# RL78G10_FOOT_A2.net
KiCad netlist of a schematic drawn in EAGLE
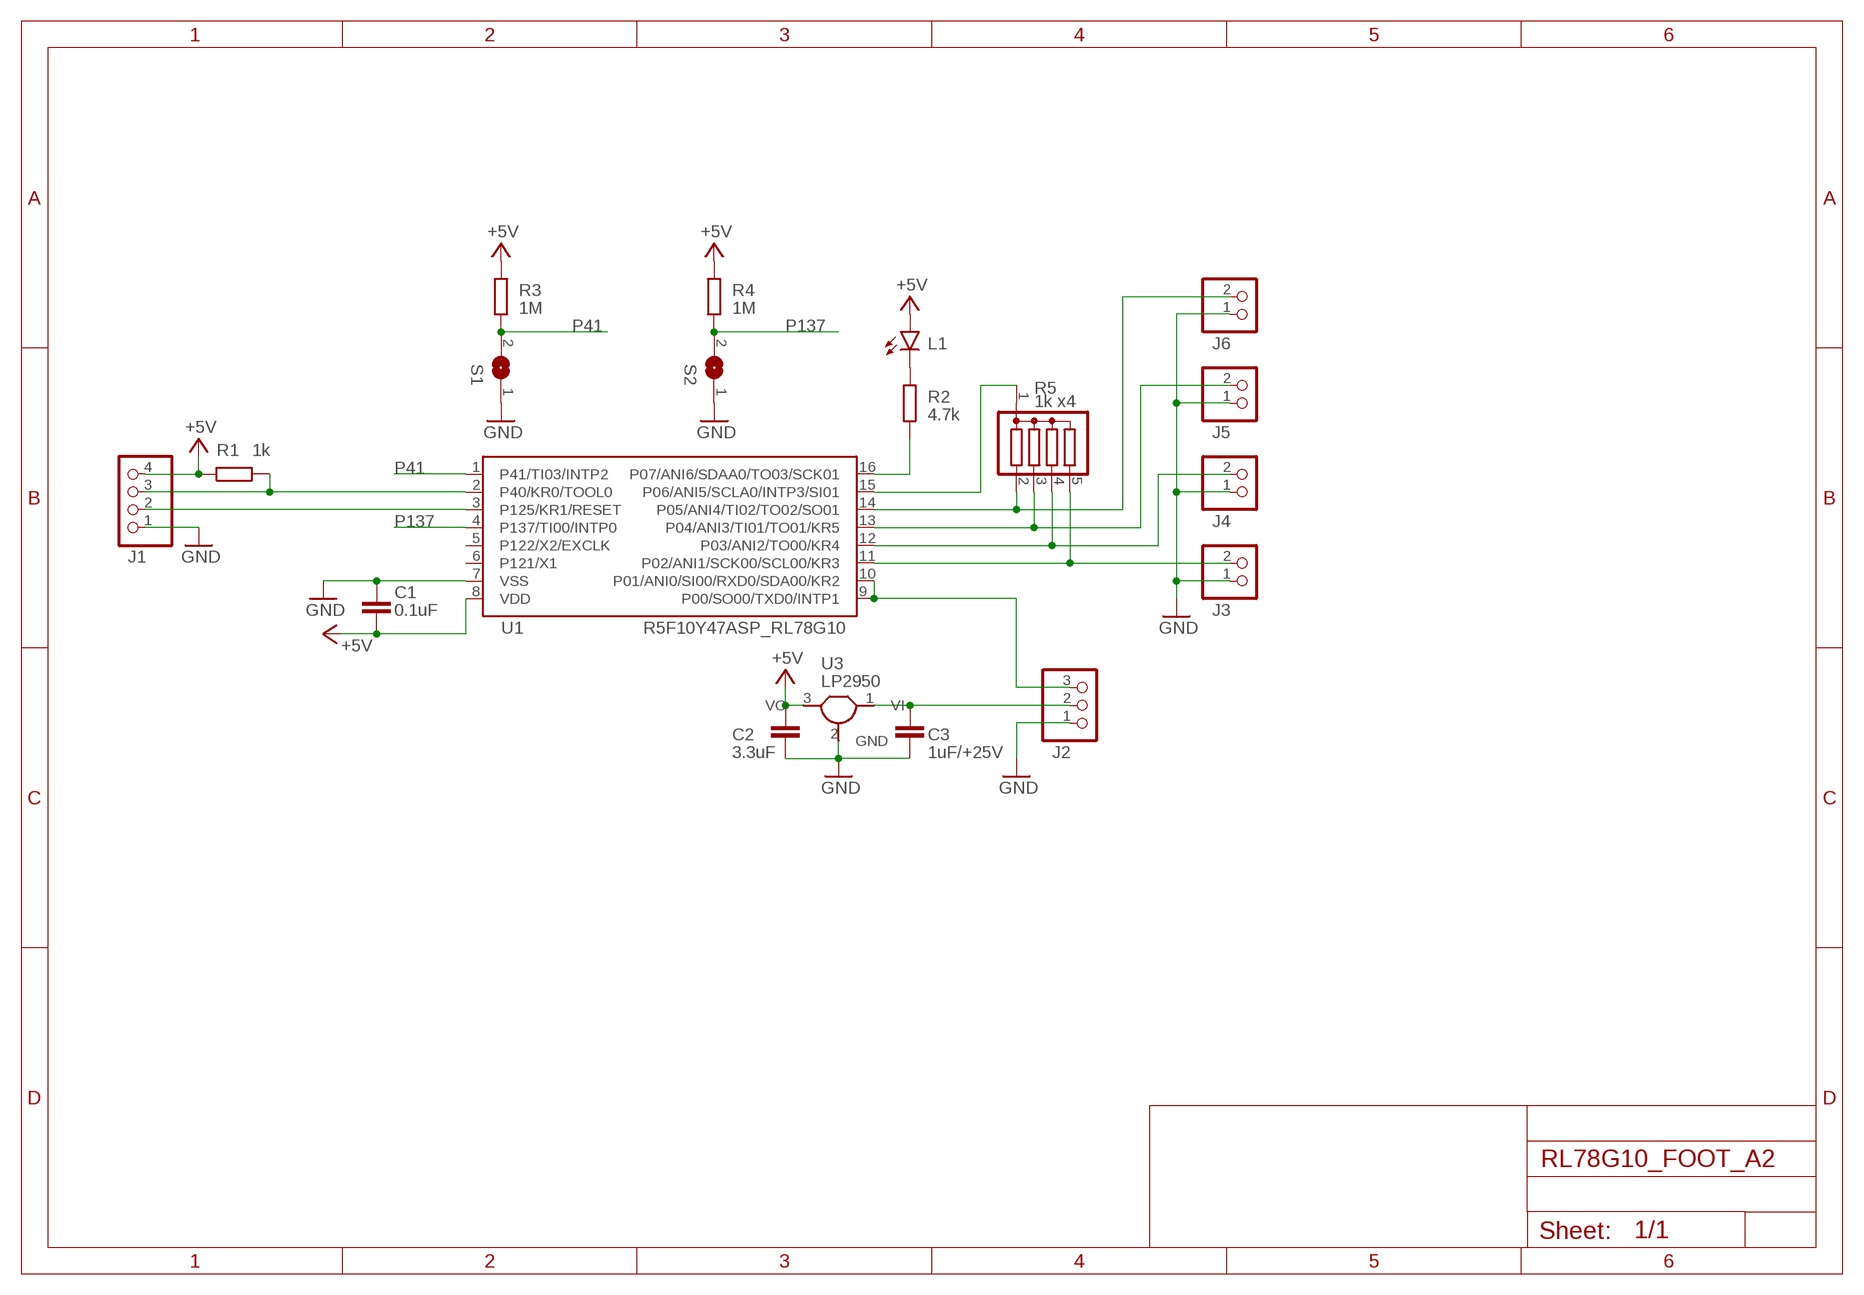
[diagram p0: schematic, sheet 1]

(export (version "E")
  (design (tool "Eeschema 10.0.6"))
  (components
    (comp (ref "C1")
      (value "0.1uF")
      (footprint "eagle-import:C0603")
      (libsource (lib "eagle-import") (part "C-EUC0603"))
    )
    (comp (ref "C2")
      (value "3.3uF")
      (footprint "eagle-import:C0805")
      (libsource (lib "eagle-import") (part "C-EUC0805"))
    )
    (comp (ref "C3")
      (value "1uF/+25V")
      (footprint "eagle-import:C0805")
      (libsource (lib "eagle-import") (part "C-EUC0805"))
    )
    (comp (ref "J1")
      (value "PINHD_1X4")
      (footprint "eagle-import:PINHD_1X04")
      (libsource (lib "eagle-import") (part "PINHD_1X4"))
    )
    (comp (ref "J2")
      (value "PINHD_1X3")
      (footprint "eagle-import:PINHD_1X03")
      (libsource (lib "eagle-import") (part "PINHD_1X3"))
    )
    (comp (ref "J3")
      (value "PINHD_1X2")
      (footprint "eagle-import:PINHD_1X02")
      (libsource (lib "eagle-import") (part "PINHD_1X2"))
    )
    (comp (ref "J4")
      (value "PINHD_1X2")
      (footprint "eagle-import:PINHD_1X02")
      (libsource (lib "eagle-import") (part "PINHD_1X2"))
    )
    (comp (ref "J5")
      (value "PINHD_1X2")
      (footprint "eagle-import:PINHD_1X02")
      (libsource (lib "eagle-import") (part "PINHD_1X2"))
    )
    (comp (ref "J6")
      (value "PINHD_1X2")
      (footprint "eagle-import:PINHD_1X02")
      (libsource (lib "eagle-import") (part "PINHD_1X2"))
    )
    (comp (ref "L1")
      (value "LEDSML0603")
      (footprint "eagle-import:SML0603")
      (libsource (lib "eagle-import") (part "LEDSML0603"))
    )
    (comp (ref "R1")
      (value "1k")
      (footprint "eagle-import:R0603")
      (libsource (lib "eagle-import") (part "R-EU_R0603"))
    )
    (comp (ref "R2")
      (value "4.7k")
      (footprint "eagle-import:R0603")
      (libsource (lib "eagle-import") (part "R-EU_R0603"))
    )
    (comp (ref "R3")
      (value "1M")
      (footprint "eagle-import:R0603")
      (libsource (lib "eagle-import") (part "R-EU_R0603"))
    )
    (comp (ref "R4")
      (value "1M")
      (footprint "eagle-import:R0603")
      (libsource (lib "eagle-import") (part "R-EU_R0603"))
    )
    (comp (ref "R5")
      (value "1k x4")
      (footprint "eagle-import:SIL5")
      (libsource (lib "eagle-import") (part "G04R"))
    )
    (comp (ref "S1")
      (value "SJ-OMINI")
      (footprint "eagle-import:SJ-O")
      (libsource (lib "eagle-import") (part "SJ-OMINI"))
    )
    (comp (ref "S2")
      (value "SJ-OMINI")
      (footprint "eagle-import:SJ-O")
      (libsource (lib "eagle-import") (part "SJ-OMINI"))
    )
    (comp (ref "U1")
      (value "R5F10Y47ASP_RL78G10")
      (footprint "eagle-import:SSOP16")
      (libsource (lib "eagle-import") (part "RL78/G10_16"))
    )
    (comp (ref "U3")
      (value "LP2950")
      (footprint "eagle-import:TO92-")
      (libsource (lib "eagle-import") (part "LP2950"))
    )
  )
  (nets
    (net (code "1") (name "+5V") (class "Default")
      (node (ref "C1") (pin "2") (pinfunction "2_2") (pintype "passive"))
      (node (ref "C2") (pin "1") (pinfunction "1_1") (pintype "passive"))
      (node (ref "J1") (pin "4") (pinfunction "4_4") (pintype "passive"))
      (node (ref "L1") (pin "A") (pinfunction "A_A") (pintype "passive"))
      (node (ref "R1") (pin "1") (pinfunction "1_1") (pintype "passive"))
      (node (ref "R3") (pin "1") (pinfunction "1_1") (pintype "passive"))
      (node (ref "R4") (pin "1") (pinfunction "1_1") (pintype "passive"))
      (node (ref "U1") (pin "8") (pinfunction "VDD_8") (pintype "bidirectional"))
      (node (ref "U3") (pin "3") (pinfunction "VO_3") (pintype "output"))
    )
    (net (code "2") (name "/P41") (class "Default")
      (node (ref "R3") (pin "2") (pinfunction "2_2") (pintype "passive"))
      (node (ref "S1") (pin "2") (pinfunction "2_2") (pintype "passive"))
      (node (ref "U1") (pin "1") (pinfunction "P41/TI03/INTP2_1") (pintype "bidirectional"))
    )
    (net (code "3") (name "/P137") (class "Default")
      (node (ref "R4") (pin "2") (pinfunction "2_2") (pintype "passive"))
      (node (ref "S2") (pin "2") (pinfunction "2_2") (pintype "passive"))
      (node (ref "U1") (pin "4") (pinfunction "P137/TI00/INTP0_4") (pintype "bidirectional"))
    )
    (net (code "4") (name "GND") (class "Default")
      (node (ref "C1") (pin "1") (pinfunction "1_1") (pintype "passive"))
      (node (ref "C2") (pin "2") (pinfunction "2_2") (pintype "passive"))
      (node (ref "C3") (pin "2") (pinfunction "2_2") (pintype "passive"))
      (node (ref "J1") (pin "1") (pinfunction "1_1") (pintype "passive"))
      (node (ref "J2") (pin "1") (pinfunction "1_1") (pintype "passive"))
      (node (ref "J3") (pin "1") (pinfunction "1_1") (pintype "passive"))
      (node (ref "J4") (pin "1") (pinfunction "1_1") (pintype "passive"))
      (node (ref "J5") (pin "1") (pinfunction "1_1") (pintype "passive"))
      (node (ref "J6") (pin "1") (pinfunction "1_1") (pintype "passive"))
      (node (ref "S1") (pin "1") (pinfunction "1_1") (pintype "passive"))
      (node (ref "S2") (pin "1") (pinfunction "1_1") (pintype "passive"))
      (node (ref "U1") (pin "7") (pinfunction "VSS_7") (pintype "bidirectional"))
      (node (ref "U3") (pin "2") (pinfunction "GND_2") (pintype "bidirectional"))
    )
    (net (code "5") (name "Net-(L1-PadC)") (class "Default")
      (node (ref "L1") (pin "C") (pinfunction "C_C") (pintype "passive"))
      (node (ref "R2") (pin "1") (pinfunction "1_1") (pintype "passive"))
    )
    (net (code "6") (name "Net-(U1-P00{slash}SO00{slash}TXD0{slash}INTP1)") (class "Default")
      (node (ref "J2") (pin "3") (pinfunction "3_3") (pintype "passive"))
      (node (ref "U1") (pin "10") (pinfunction "P01/ANI0/SI00/RXD0/SDA00/KR2_10") (pintype "bidirectional"))
      (node (ref "U1") (pin "9") (pinfunction "P00/SO00/TXD0/INTP1_9") (pintype "bidirectional"))
    )
    (net (code "7") (name "Net-(U1-P02{slash}ANI1{slash}SCK00{slash}SCL00{slash}KR3)") (class "Default")
      (node (ref "J3") (pin "2") (pinfunction "2_2") (pintype "passive"))
      (node (ref "R5") (pin "5") (pinfunction "5_5") (pintype "passive"))
      (node (ref "U1") (pin "11") (pinfunction "P02/ANI1/SCK00/SCL00/KR3_11") (pintype "bidirectional"))
    )
    (net (code "8") (name "Net-(U1-P03{slash}ANI2{slash}TO00{slash}KR4)") (class "Default")
      (node (ref "J4") (pin "2") (pinfunction "2_2") (pintype "passive"))
      (node (ref "R5") (pin "4") (pinfunction "4_4") (pintype "passive"))
      (node (ref "U1") (pin "12") (pinfunction "P03/ANI2/TO00/KR4_12") (pintype "bidirectional"))
    )
    (net (code "9") (name "Net-(U1-P04{slash}ANI3{slash}TI01{slash}TO01{slash}KR5)") (class "Default")
      (node (ref "J5") (pin "2") (pinfunction "2_2") (pintype "passive"))
      (node (ref "R5") (pin "3") (pinfunction "3_3") (pintype "passive"))
      (node (ref "U1") (pin "13") (pinfunction "P04/ANI3/TI01/TO01/KR5_13") (pintype "bidirectional"))
    )
    (net (code "10") (name "Net-(U1-P05{slash}ANI4{slash}TI02{slash}TO02{slash}SO01)") (class "Default")
      (node (ref "J6") (pin "2") (pinfunction "2_2") (pintype "passive"))
      (node (ref "R5") (pin "2") (pinfunction "2_2") (pintype "passive"))
      (node (ref "U1") (pin "14") (pinfunction "P05/ANI4/TI02/TO02/SO01_14") (pintype "bidirectional"))
    )
    (net (code "11") (name "Net-(U1-P06{slash}ANI5{slash}SCLA0{slash}INTP3{slash}SI01)") (class "Default")
      (node (ref "R5") (pin "1") (pinfunction "1_1") (pintype "passive"))
      (node (ref "U1") (pin "15") (pinfunction "P06/ANI5/SCLA0/INTP3/SI01_15") (pintype "bidirectional"))
    )
    (net (code "12") (name "Net-(U1-P07{slash}ANI6{slash}SDAA0{slash}TO03{slash}SCK01)") (class "Default")
      (node (ref "R2") (pin "2") (pinfunction "2_2") (pintype "passive"))
      (node (ref "U1") (pin "16") (pinfunction "P07/ANI6/SDAA0/TO03/SCK01_16") (pintype "bidirectional"))
    )
    (net (code "13") (name "Net-(U1-P40{slash}KR0{slash}TOOL0)") (class "Default")
      (node (ref "J1") (pin "3") (pinfunction "3_3") (pintype "passive"))
      (node (ref "R1") (pin "2") (pinfunction "2_2") (pintype "passive"))
      (node (ref "U1") (pin "2") (pinfunction "P40/KR0/TOOL0_2") (pintype "bidirectional"))
    )
    (net (code "14") (name "Net-(U1-P125{slash}KR1{slash}RESET)") (class "Default")
      (node (ref "J1") (pin "2") (pinfunction "2_2") (pintype "passive"))
      (node (ref "U1") (pin "3") (pinfunction "P125/KR1/RESET_3") (pintype "bidirectional"))
    )
    (net (code "15") (name "Net-(U3-VI)") (class "Default")
      (node (ref "C3") (pin "1") (pinfunction "1_1") (pintype "passive"))
      (node (ref "J2") (pin "2") (pinfunction "2_2") (pintype "passive"))
      (node (ref "U3") (pin "1") (pinfunction "VI_1") (pintype "input"))
    )
    (net (code "16") (name "unconnected-(U1-P121{slash}X1-Pad6)") (class "Default")
      (node (ref "U1") (pin "6") (pinfunction "P121/X1_6") (pintype "bidirectional"))
    )
    (net (code "17") (name "unconnected-(U1-P122{slash}X2{slash}EXCLK-Pad5)") (class "Default")
      (node (ref "U1") (pin "5") (pinfunction "P122/X2/EXCLK_5") (pintype "bidirectional"))
    )
  )
)
